# 14A-006.net
KiCad netlist of a schematic drawn in EAGLE
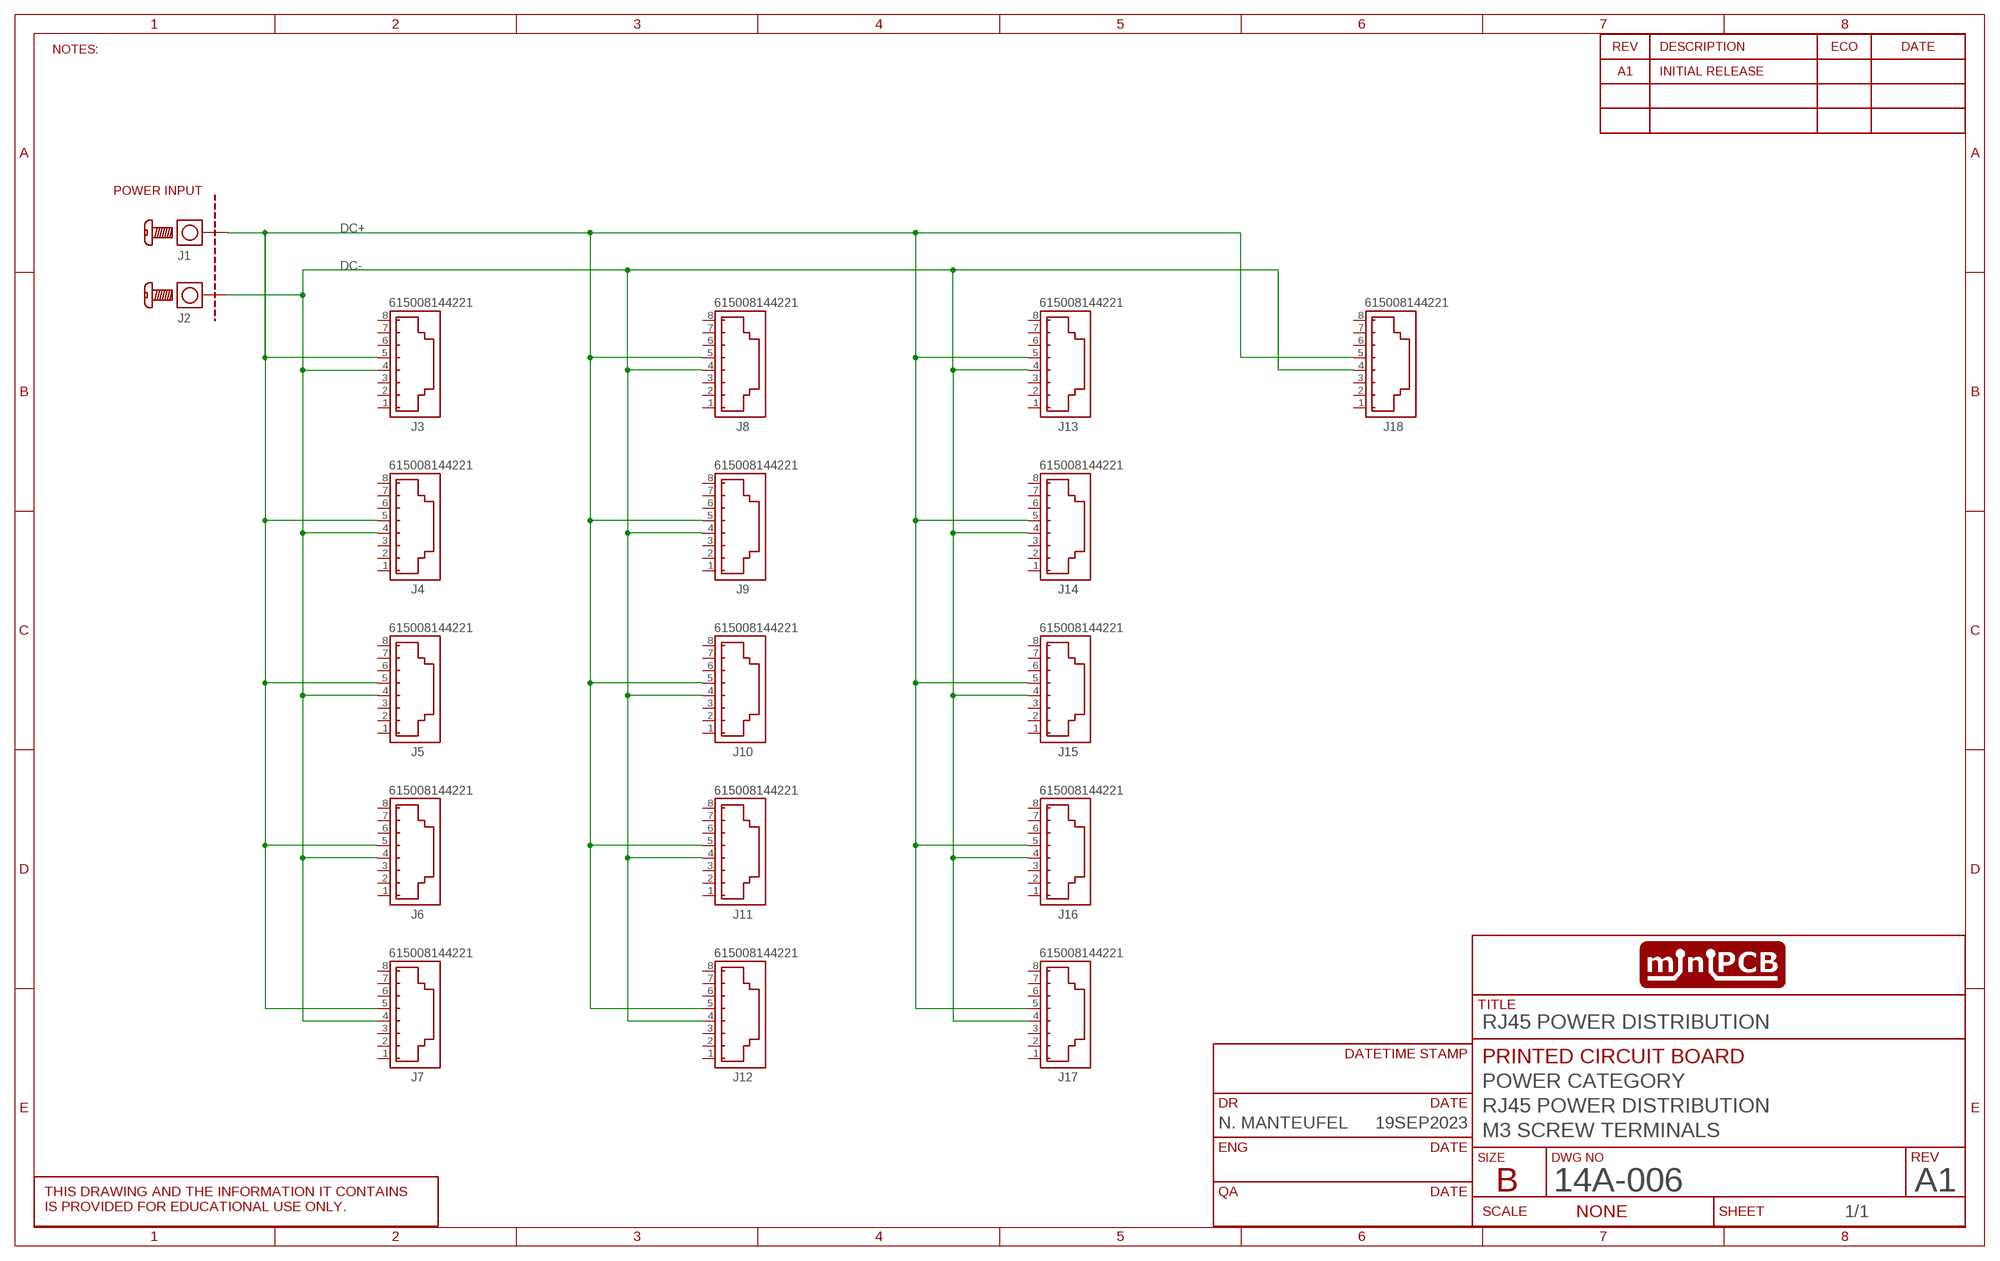
[diagram p0: schematic, sheet 1]

(export (version "E")
  (design (tool "Eeschema 10.0.6"))
  (components
    (comp (ref "-")
      (value "POWER INPUT")
      (footprint "eagle-import:MINIPCB_DOCK_50X100")
      (fields (field (name "NAME1") "RJ45 POWER DISTRIBUTION") (field (name "PART_NUMBER") "14A-006"))
      (libsource (lib "eagle-import") (part "MINIPCB_0PDOCK_50X100"))
    )
    (comp (ref "J1")
      (value "SCREW-TERMINAL")
      (footprint "eagle-import:SCREW-TERMINAL-M3")
      (libsource (lib "eagle-import") (part "SCREW-TERMINAL"))
    )
    (comp (ref "J2")
      (value "SCREW-TERMINAL")
      (footprint "eagle-import:SCREW-TERMINAL-M3")
      (libsource (lib "eagle-import") (part "SCREW-TERMINAL"))
    )
    (comp (ref "J3")
      (value "615008144221")
      (footprint "eagle-import:615008144221")
      (libsource (lib "eagle-import") (part "615008144221"))
    )
    (comp (ref "J4")
      (value "615008144221")
      (footprint "eagle-import:615008144221")
      (libsource (lib "eagle-import") (part "615008144221"))
    )
    (comp (ref "J5")
      (value "615008144221")
      (footprint "eagle-import:615008144221")
      (libsource (lib "eagle-import") (part "615008144221"))
    )
    (comp (ref "J6")
      (value "615008144221")
      (footprint "eagle-import:615008144221")
      (libsource (lib "eagle-import") (part "615008144221"))
    )
    (comp (ref "J7")
      (value "615008144221")
      (footprint "eagle-import:615008144221")
      (libsource (lib "eagle-import") (part "615008144221"))
    )
    (comp (ref "J8")
      (value "615008144221")
      (footprint "eagle-import:615008144221")
      (libsource (lib "eagle-import") (part "615008144221"))
    )
    (comp (ref "J9")
      (value "615008144221")
      (footprint "eagle-import:615008144221")
      (libsource (lib "eagle-import") (part "615008144221"))
    )
    (comp (ref "J10")
      (value "615008144221")
      (footprint "eagle-import:615008144221")
      (libsource (lib "eagle-import") (part "615008144221"))
    )
    (comp (ref "J11")
      (value "615008144221")
      (footprint "eagle-import:615008144221")
      (libsource (lib "eagle-import") (part "615008144221"))
    )
    (comp (ref "J12")
      (value "615008144221")
      (footprint "eagle-import:615008144221")
      (libsource (lib "eagle-import") (part "615008144221"))
    )
    (comp (ref "J13")
      (value "615008144221")
      (footprint "eagle-import:615008144221")
      (libsource (lib "eagle-import") (part "615008144221"))
    )
    (comp (ref "J14")
      (value "615008144221")
      (footprint "eagle-import:615008144221")
      (libsource (lib "eagle-import") (part "615008144221"))
    )
    (comp (ref "J15")
      (value "615008144221")
      (footprint "eagle-import:615008144221")
      (libsource (lib "eagle-import") (part "615008144221"))
    )
    (comp (ref "J16")
      (value "615008144221")
      (footprint "eagle-import:615008144221")
      (libsource (lib "eagle-import") (part "615008144221"))
    )
    (comp (ref "J17")
      (value "615008144221")
      (footprint "eagle-import:615008144221")
      (libsource (lib "eagle-import") (part "615008144221"))
    )
    (comp (ref "J18")
      (value "615008144221")
      (footprint "eagle-import:615008144221")
      (libsource (lib "eagle-import") (part "615008144221"))
    )
  )
  (nets
    (net (code "1") (name "/DC+") (class "Default")
      (node (ref "J1") (pin "1") (pinfunction "1_1") (pintype "bidirectional"))
      (node (ref "J1") (pin "2") (pinfunction "1_2") (pintype "bidirectional"))
      (node (ref "J1") (pin "3") (pinfunction "1_3") (pintype "bidirectional"))
      (node (ref "J1") (pin "4") (pinfunction "1_4") (pintype "bidirectional"))
      (node (ref "J10") (pin "5") (pinfunction "4_5") (pintype "passive"))
      (node (ref "J11") (pin "5") (pinfunction "4_5") (pintype "passive"))
      (node (ref "J12") (pin "5") (pinfunction "4_5") (pintype "passive"))
      (node (ref "J13") (pin "5") (pinfunction "4_5") (pintype "passive"))
      (node (ref "J14") (pin "5") (pinfunction "4_5") (pintype "passive"))
      (node (ref "J15") (pin "5") (pinfunction "4_5") (pintype "passive"))
      (node (ref "J16") (pin "5") (pinfunction "4_5") (pintype "passive"))
      (node (ref "J17") (pin "5") (pinfunction "4_5") (pintype "passive"))
      (node (ref "J18") (pin "5") (pinfunction "4_5") (pintype "passive"))
      (node (ref "J3") (pin "5") (pinfunction "4_5") (pintype "passive"))
      (node (ref "J4") (pin "5") (pinfunction "4_5") (pintype "passive"))
      (node (ref "J5") (pin "5") (pinfunction "4_5") (pintype "passive"))
      (node (ref "J6") (pin "5") (pinfunction "4_5") (pintype "passive"))
      (node (ref "J7") (pin "5") (pinfunction "4_5") (pintype "passive"))
      (node (ref "J8") (pin "5") (pinfunction "4_5") (pintype "passive"))
      (node (ref "J9") (pin "5") (pinfunction "4_5") (pintype "passive"))
    )
    (net (code "2") (name "/DC-") (class "Default")
      (node (ref "J10") (pin "4") (pinfunction "5_4") (pintype "passive"))
      (node (ref "J11") (pin "4") (pinfunction "5_4") (pintype "passive"))
      (node (ref "J12") (pin "4") (pinfunction "5_4") (pintype "passive"))
      (node (ref "J13") (pin "4") (pinfunction "5_4") (pintype "passive"))
      (node (ref "J14") (pin "4") (pinfunction "5_4") (pintype "passive"))
      (node (ref "J15") (pin "4") (pinfunction "5_4") (pintype "passive"))
      (node (ref "J16") (pin "4") (pinfunction "5_4") (pintype "passive"))
      (node (ref "J17") (pin "4") (pinfunction "5_4") (pintype "passive"))
      (node (ref "J18") (pin "4") (pinfunction "5_4") (pintype "passive"))
      (node (ref "J2") (pin "1") (pinfunction "1_1") (pintype "bidirectional"))
      (node (ref "J2") (pin "2") (pinfunction "1_2") (pintype "bidirectional"))
      (node (ref "J2") (pin "3") (pinfunction "1_3") (pintype "bidirectional"))
      (node (ref "J2") (pin "4") (pinfunction "1_4") (pintype "bidirectional"))
      (node (ref "J3") (pin "4") (pinfunction "5_4") (pintype "passive"))
      (node (ref "J4") (pin "4") (pinfunction "5_4") (pintype "passive"))
      (node (ref "J5") (pin "4") (pinfunction "5_4") (pintype "passive"))
      (node (ref "J6") (pin "4") (pinfunction "5_4") (pintype "passive"))
      (node (ref "J7") (pin "4") (pinfunction "5_4") (pintype "passive"))
      (node (ref "J8") (pin "4") (pinfunction "5_4") (pintype "passive"))
      (node (ref "J9") (pin "4") (pinfunction "5_4") (pintype "passive"))
    )
    (net (code "3") (name "unconnected-(J3-1-Pad8)") (class "Default")
      (node (ref "J3") (pin "8") (pinfunction "1_8") (pintype "passive"))
    )
    (net (code "4") (name "unconnected-(J3-2-Pad7)") (class "Default")
      (node (ref "J3") (pin "7") (pinfunction "2_7") (pintype "passive"))
    )
    (net (code "5") (name "unconnected-(J3-3-Pad6)") (class "Default")
      (node (ref "J3") (pin "6") (pinfunction "3_6") (pintype "passive"))
    )
    (net (code "6") (name "unconnected-(J3-6-Pad3)") (class "Default")
      (node (ref "J3") (pin "3") (pinfunction "6_3") (pintype "passive"))
    )
    (net (code "7") (name "unconnected-(J3-7-Pad2)") (class "Default")
      (node (ref "J3") (pin "2") (pinfunction "7_2") (pintype "passive"))
    )
    (net (code "8") (name "unconnected-(J3-8-Pad1)") (class "Default")
      (node (ref "J3") (pin "1") (pinfunction "8_1") (pintype "passive"))
    )
    (net (code "9") (name "unconnected-(J4-1-Pad8)") (class "Default")
      (node (ref "J4") (pin "8") (pinfunction "1_8") (pintype "passive"))
    )
    (net (code "10") (name "unconnected-(J4-2-Pad7)") (class "Default")
      (node (ref "J4") (pin "7") (pinfunction "2_7") (pintype "passive"))
    )
    (net (code "11") (name "unconnected-(J4-3-Pad6)") (class "Default")
      (node (ref "J4") (pin "6") (pinfunction "3_6") (pintype "passive"))
    )
    (net (code "12") (name "unconnected-(J4-6-Pad3)") (class "Default")
      (node (ref "J4") (pin "3") (pinfunction "6_3") (pintype "passive"))
    )
    (net (code "13") (name "unconnected-(J4-7-Pad2)") (class "Default")
      (node (ref "J4") (pin "2") (pinfunction "7_2") (pintype "passive"))
    )
    (net (code "14") (name "unconnected-(J4-8-Pad1)") (class "Default")
      (node (ref "J4") (pin "1") (pinfunction "8_1") (pintype "passive"))
    )
    (net (code "15") (name "unconnected-(J5-1-Pad8)") (class "Default")
      (node (ref "J5") (pin "8") (pinfunction "1_8") (pintype "passive"))
    )
    (net (code "16") (name "unconnected-(J5-2-Pad7)") (class "Default")
      (node (ref "J5") (pin "7") (pinfunction "2_7") (pintype "passive"))
    )
    (net (code "17") (name "unconnected-(J5-3-Pad6)") (class "Default")
      (node (ref "J5") (pin "6") (pinfunction "3_6") (pintype "passive"))
    )
    (net (code "18") (name "unconnected-(J5-6-Pad3)") (class "Default")
      (node (ref "J5") (pin "3") (pinfunction "6_3") (pintype "passive"))
    )
    (net (code "19") (name "unconnected-(J5-7-Pad2)") (class "Default")
      (node (ref "J5") (pin "2") (pinfunction "7_2") (pintype "passive"))
    )
    (net (code "20") (name "unconnected-(J5-8-Pad1)") (class "Default")
      (node (ref "J5") (pin "1") (pinfunction "8_1") (pintype "passive"))
    )
    (net (code "21") (name "unconnected-(J6-1-Pad8)") (class "Default")
      (node (ref "J6") (pin "8") (pinfunction "1_8") (pintype "passive"))
    )
    (net (code "22") (name "unconnected-(J6-2-Pad7)") (class "Default")
      (node (ref "J6") (pin "7") (pinfunction "2_7") (pintype "passive"))
    )
    (net (code "23") (name "unconnected-(J6-3-Pad6)") (class "Default")
      (node (ref "J6") (pin "6") (pinfunction "3_6") (pintype "passive"))
    )
    (net (code "24") (name "unconnected-(J6-6-Pad3)") (class "Default")
      (node (ref "J6") (pin "3") (pinfunction "6_3") (pintype "passive"))
    )
    (net (code "25") (name "unconnected-(J6-7-Pad2)") (class "Default")
      (node (ref "J6") (pin "2") (pinfunction "7_2") (pintype "passive"))
    )
    (net (code "26") (name "unconnected-(J6-8-Pad1)") (class "Default")
      (node (ref "J6") (pin "1") (pinfunction "8_1") (pintype "passive"))
    )
    (net (code "27") (name "unconnected-(J7-1-Pad8)") (class "Default")
      (node (ref "J7") (pin "8") (pinfunction "1_8") (pintype "passive"))
    )
    (net (code "28") (name "unconnected-(J7-2-Pad7)") (class "Default")
      (node (ref "J7") (pin "7") (pinfunction "2_7") (pintype "passive"))
    )
    (net (code "29") (name "unconnected-(J7-3-Pad6)") (class "Default")
      (node (ref "J7") (pin "6") (pinfunction "3_6") (pintype "passive"))
    )
    (net (code "30") (name "unconnected-(J7-6-Pad3)") (class "Default")
      (node (ref "J7") (pin "3") (pinfunction "6_3") (pintype "passive"))
    )
    (net (code "31") (name "unconnected-(J7-7-Pad2)") (class "Default")
      (node (ref "J7") (pin "2") (pinfunction "7_2") (pintype "passive"))
    )
    (net (code "32") (name "unconnected-(J7-8-Pad1)") (class "Default")
      (node (ref "J7") (pin "1") (pinfunction "8_1") (pintype "passive"))
    )
    (net (code "33") (name "unconnected-(J8-1-Pad8)") (class "Default")
      (node (ref "J8") (pin "8") (pinfunction "1_8") (pintype "passive"))
    )
    (net (code "34") (name "unconnected-(J8-2-Pad7)") (class "Default")
      (node (ref "J8") (pin "7") (pinfunction "2_7") (pintype "passive"))
    )
    (net (code "35") (name "unconnected-(J8-3-Pad6)") (class "Default")
      (node (ref "J8") (pin "6") (pinfunction "3_6") (pintype "passive"))
    )
    (net (code "36") (name "unconnected-(J8-6-Pad3)") (class "Default")
      (node (ref "J8") (pin "3") (pinfunction "6_3") (pintype "passive"))
    )
    (net (code "37") (name "unconnected-(J8-7-Pad2)") (class "Default")
      (node (ref "J8") (pin "2") (pinfunction "7_2") (pintype "passive"))
    )
    (net (code "38") (name "unconnected-(J8-8-Pad1)") (class "Default")
      (node (ref "J8") (pin "1") (pinfunction "8_1") (pintype "passive"))
    )
    (net (code "39") (name "unconnected-(J9-1-Pad8)") (class "Default")
      (node (ref "J9") (pin "8") (pinfunction "1_8") (pintype "passive"))
    )
    (net (code "40") (name "unconnected-(J9-2-Pad7)") (class "Default")
      (node (ref "J9") (pin "7") (pinfunction "2_7") (pintype "passive"))
    )
    (net (code "41") (name "unconnected-(J9-3-Pad6)") (class "Default")
      (node (ref "J9") (pin "6") (pinfunction "3_6") (pintype "passive"))
    )
    (net (code "42") (name "unconnected-(J9-6-Pad3)") (class "Default")
      (node (ref "J9") (pin "3") (pinfunction "6_3") (pintype "passive"))
    )
    (net (code "43") (name "unconnected-(J9-7-Pad2)") (class "Default")
      (node (ref "J9") (pin "2") (pinfunction "7_2") (pintype "passive"))
    )
    (net (code "44") (name "unconnected-(J9-8-Pad1)") (class "Default")
      (node (ref "J9") (pin "1") (pinfunction "8_1") (pintype "passive"))
    )
    (net (code "45") (name "unconnected-(J10-1-Pad8)") (class "Default")
      (node (ref "J10") (pin "8") (pinfunction "1_8") (pintype "passive"))
    )
    (net (code "46") (name "unconnected-(J10-2-Pad7)") (class "Default")
      (node (ref "J10") (pin "7") (pinfunction "2_7") (pintype "passive"))
    )
    (net (code "47") (name "unconnected-(J10-3-Pad6)") (class "Default")
      (node (ref "J10") (pin "6") (pinfunction "3_6") (pintype "passive"))
    )
    (net (code "48") (name "unconnected-(J10-6-Pad3)") (class "Default")
      (node (ref "J10") (pin "3") (pinfunction "6_3") (pintype "passive"))
    )
    (net (code "49") (name "unconnected-(J10-7-Pad2)") (class "Default")
      (node (ref "J10") (pin "2") (pinfunction "7_2") (pintype "passive"))
    )
    (net (code "50") (name "unconnected-(J10-8-Pad1)") (class "Default")
      (node (ref "J10") (pin "1") (pinfunction "8_1") (pintype "passive"))
    )
    (net (code "51") (name "unconnected-(J11-1-Pad8)") (class "Default")
      (node (ref "J11") (pin "8") (pinfunction "1_8") (pintype "passive"))
    )
    (net (code "52") (name "unconnected-(J11-2-Pad7)") (class "Default")
      (node (ref "J11") (pin "7") (pinfunction "2_7") (pintype "passive"))
    )
    (net (code "53") (name "unconnected-(J11-3-Pad6)") (class "Default")
      (node (ref "J11") (pin "6") (pinfunction "3_6") (pintype "passive"))
    )
    (net (code "54") (name "unconnected-(J11-6-Pad3)") (class "Default")
      (node (ref "J11") (pin "3") (pinfunction "6_3") (pintype "passive"))
    )
    (net (code "55") (name "unconnected-(J11-7-Pad2)") (class "Default")
      (node (ref "J11") (pin "2") (pinfunction "7_2") (pintype "passive"))
    )
    (net (code "56") (name "unconnected-(J11-8-Pad1)") (class "Default")
      (node (ref "J11") (pin "1") (pinfunction "8_1") (pintype "passive"))
    )
    (net (code "57") (name "unconnected-(J12-1-Pad8)") (class "Default")
      (node (ref "J12") (pin "8") (pinfunction "1_8") (pintype "passive"))
    )
    (net (code "58") (name "unconnected-(J12-2-Pad7)") (class "Default")
      (node (ref "J12") (pin "7") (pinfunction "2_7") (pintype "passive"))
    )
    (net (code "59") (name "unconnected-(J12-3-Pad6)") (class "Default")
      (node (ref "J12") (pin "6") (pinfunction "3_6") (pintype "passive"))
    )
    (net (code "60") (name "unconnected-(J12-6-Pad3)") (class "Default")
      (node (ref "J12") (pin "3") (pinfunction "6_3") (pintype "passive"))
    )
    (net (code "61") (name "unconnected-(J12-7-Pad2)") (class "Default")
      (node (ref "J12") (pin "2") (pinfunction "7_2") (pintype "passive"))
    )
    (net (code "62") (name "unconnected-(J12-8-Pad1)") (class "Default")
      (node (ref "J12") (pin "1") (pinfunction "8_1") (pintype "passive"))
    )
    (net (code "63") (name "unconnected-(J13-1-Pad8)") (class "Default")
      (node (ref "J13") (pin "8") (pinfunction "1_8") (pintype "passive"))
    )
    (net (code "64") (name "unconnected-(J13-2-Pad7)") (class "Default")
      (node (ref "J13") (pin "7") (pinfunction "2_7") (pintype "passive"))
    )
    (net (code "65") (name "unconnected-(J13-3-Pad6)") (class "Default")
      (node (ref "J13") (pin "6") (pinfunction "3_6") (pintype "passive"))
    )
    (net (code "66") (name "unconnected-(J13-6-Pad3)") (class "Default")
      (node (ref "J13") (pin "3") (pinfunction "6_3") (pintype "passive"))
    )
    (net (code "67") (name "unconnected-(J13-7-Pad2)") (class "Default")
      (node (ref "J13") (pin "2") (pinfunction "7_2") (pintype "passive"))
    )
    (net (code "68") (name "unconnected-(J13-8-Pad1)") (class "Default")
      (node (ref "J13") (pin "1") (pinfunction "8_1") (pintype "passive"))
    )
    (net (code "69") (name "unconnected-(J14-1-Pad8)") (class "Default")
      (node (ref "J14") (pin "8") (pinfunction "1_8") (pintype "passive"))
    )
    (net (code "70") (name "unconnected-(J14-2-Pad7)") (class "Default")
      (node (ref "J14") (pin "7") (pinfunction "2_7") (pintype "passive"))
    )
    (net (code "71") (name "unconnected-(J14-3-Pad6)") (class "Default")
      (node (ref "J14") (pin "6") (pinfunction "3_6") (pintype "passive"))
    )
    (net (code "72") (name "unconnected-(J14-6-Pad3)") (class "Default")
      (node (ref "J14") (pin "3") (pinfunction "6_3") (pintype "passive"))
    )
    (net (code "73") (name "unconnected-(J14-7-Pad2)") (class "Default")
      (node (ref "J14") (pin "2") (pinfunction "7_2") (pintype "passive"))
    )
    (net (code "74") (name "unconnected-(J14-8-Pad1)") (class "Default")
      (node (ref "J14") (pin "1") (pinfunction "8_1") (pintype "passive"))
    )
    (net (code "75") (name "unconnected-(J15-1-Pad8)") (class "Default")
      (node (ref "J15") (pin "8") (pinfunction "1_8") (pintype "passive"))
    )
    (net (code "76") (name "unconnected-(J15-2-Pad7)") (class "Default")
      (node (ref "J15") (pin "7") (pinfunction "2_7") (pintype "passive"))
    )
    (net (code "77") (name "unconnected-(J15-3-Pad6)") (class "Default")
      (node (ref "J15") (pin "6") (pinfunction "3_6") (pintype "passive"))
    )
    (net (code "78") (name "unconnected-(J15-6-Pad3)") (class "Default")
      (node (ref "J15") (pin "3") (pinfunction "6_3") (pintype "passive"))
    )
    (net (code "79") (name "unconnected-(J15-7-Pad2)") (class "Default")
      (node (ref "J15") (pin "2") (pinfunction "7_2") (pintype "passive"))
    )
    (net (code "80") (name "unconnected-(J15-8-Pad1)") (class "Default")
      (node (ref "J15") (pin "1") (pinfunction "8_1") (pintype "passive"))
    )
    (net (code "81") (name "unconnected-(J16-1-Pad8)") (class "Default")
      (node (ref "J16") (pin "8") (pinfunction "1_8") (pintype "passive"))
    )
    (net (code "82") (name "unconnected-(J16-2-Pad7)") (class "Default")
      (node (ref "J16") (pin "7") (pinfunction "2_7") (pintype "passive"))
    )
    (net (code "83") (name "unconnected-(J16-3-Pad6)") (class "Default")
      (node (ref "J16") (pin "6") (pinfunction "3_6") (pintype "passive"))
    )
    (net (code "84") (name "unconnected-(J16-6-Pad3)") (class "Default")
      (node (ref "J16") (pin "3") (pinfunction "6_3") (pintype "passive"))
    )
    (net (code "85") (name "unconnected-(J16-7-Pad2)") (class "Default")
      (node (ref "J16") (pin "2") (pinfunction "7_2") (pintype "passive"))
    )
    (net (code "86") (name "unconnected-(J16-8-Pad1)") (class "Default")
      (node (ref "J16") (pin "1") (pinfunction "8_1") (pintype "passive"))
    )
    (net (code "87") (name "unconnected-(J17-1-Pad8)") (class "Default")
      (node (ref "J17") (pin "8") (pinfunction "1_8") (pintype "passive"))
    )
    (net (code "88") (name "unconnected-(J17-2-Pad7)") (class "Default")
      (node (ref "J17") (pin "7") (pinfunction "2_7") (pintype "passive"))
    )
    (net (code "89") (name "unconnected-(J17-3-Pad6)") (class "Default")
      (node (ref "J17") (pin "6") (pinfunction "3_6") (pintype "passive"))
    )
    (net (code "90") (name "unconnected-(J17-6-Pad3)") (class "Default")
      (node (ref "J17") (pin "3") (pinfunction "6_3") (pintype "passive"))
    )
    (net (code "91") (name "unconnected-(J17-7-Pad2)") (class "Default")
      (node (ref "J17") (pin "2") (pinfunction "7_2") (pintype "passive"))
    )
    (net (code "92") (name "unconnected-(J17-8-Pad1)") (class "Default")
      (node (ref "J17") (pin "1") (pinfunction "8_1") (pintype "passive"))
    )
    (net (code "93") (name "unconnected-(J18-1-Pad8)") (class "Default")
      (node (ref "J18") (pin "8") (pinfunction "1_8") (pintype "passive"))
    )
    (net (code "94") (name "unconnected-(J18-2-Pad7)") (class "Default")
      (node (ref "J18") (pin "7") (pinfunction "2_7") (pintype "passive"))
    )
    (net (code "95") (name "unconnected-(J18-3-Pad6)") (class "Default")
      (node (ref "J18") (pin "6") (pinfunction "3_6") (pintype "passive"))
    )
    (net (code "96") (name "unconnected-(J18-6-Pad3)") (class "Default")
      (node (ref "J18") (pin "3") (pinfunction "6_3") (pintype "passive"))
    )
    (net (code "97") (name "unconnected-(J18-7-Pad2)") (class "Default")
      (node (ref "J18") (pin "2") (pinfunction "7_2") (pintype "passive"))
    )
    (net (code "98") (name "unconnected-(J18-8-Pad1)") (class "Default")
      (node (ref "J18") (pin "1") (pinfunction "8_1") (pintype "passive"))
    )
  )
)
